# Moteino-IAQ-Shield.net
KiCad netlist of a schematic drawn in EAGLE
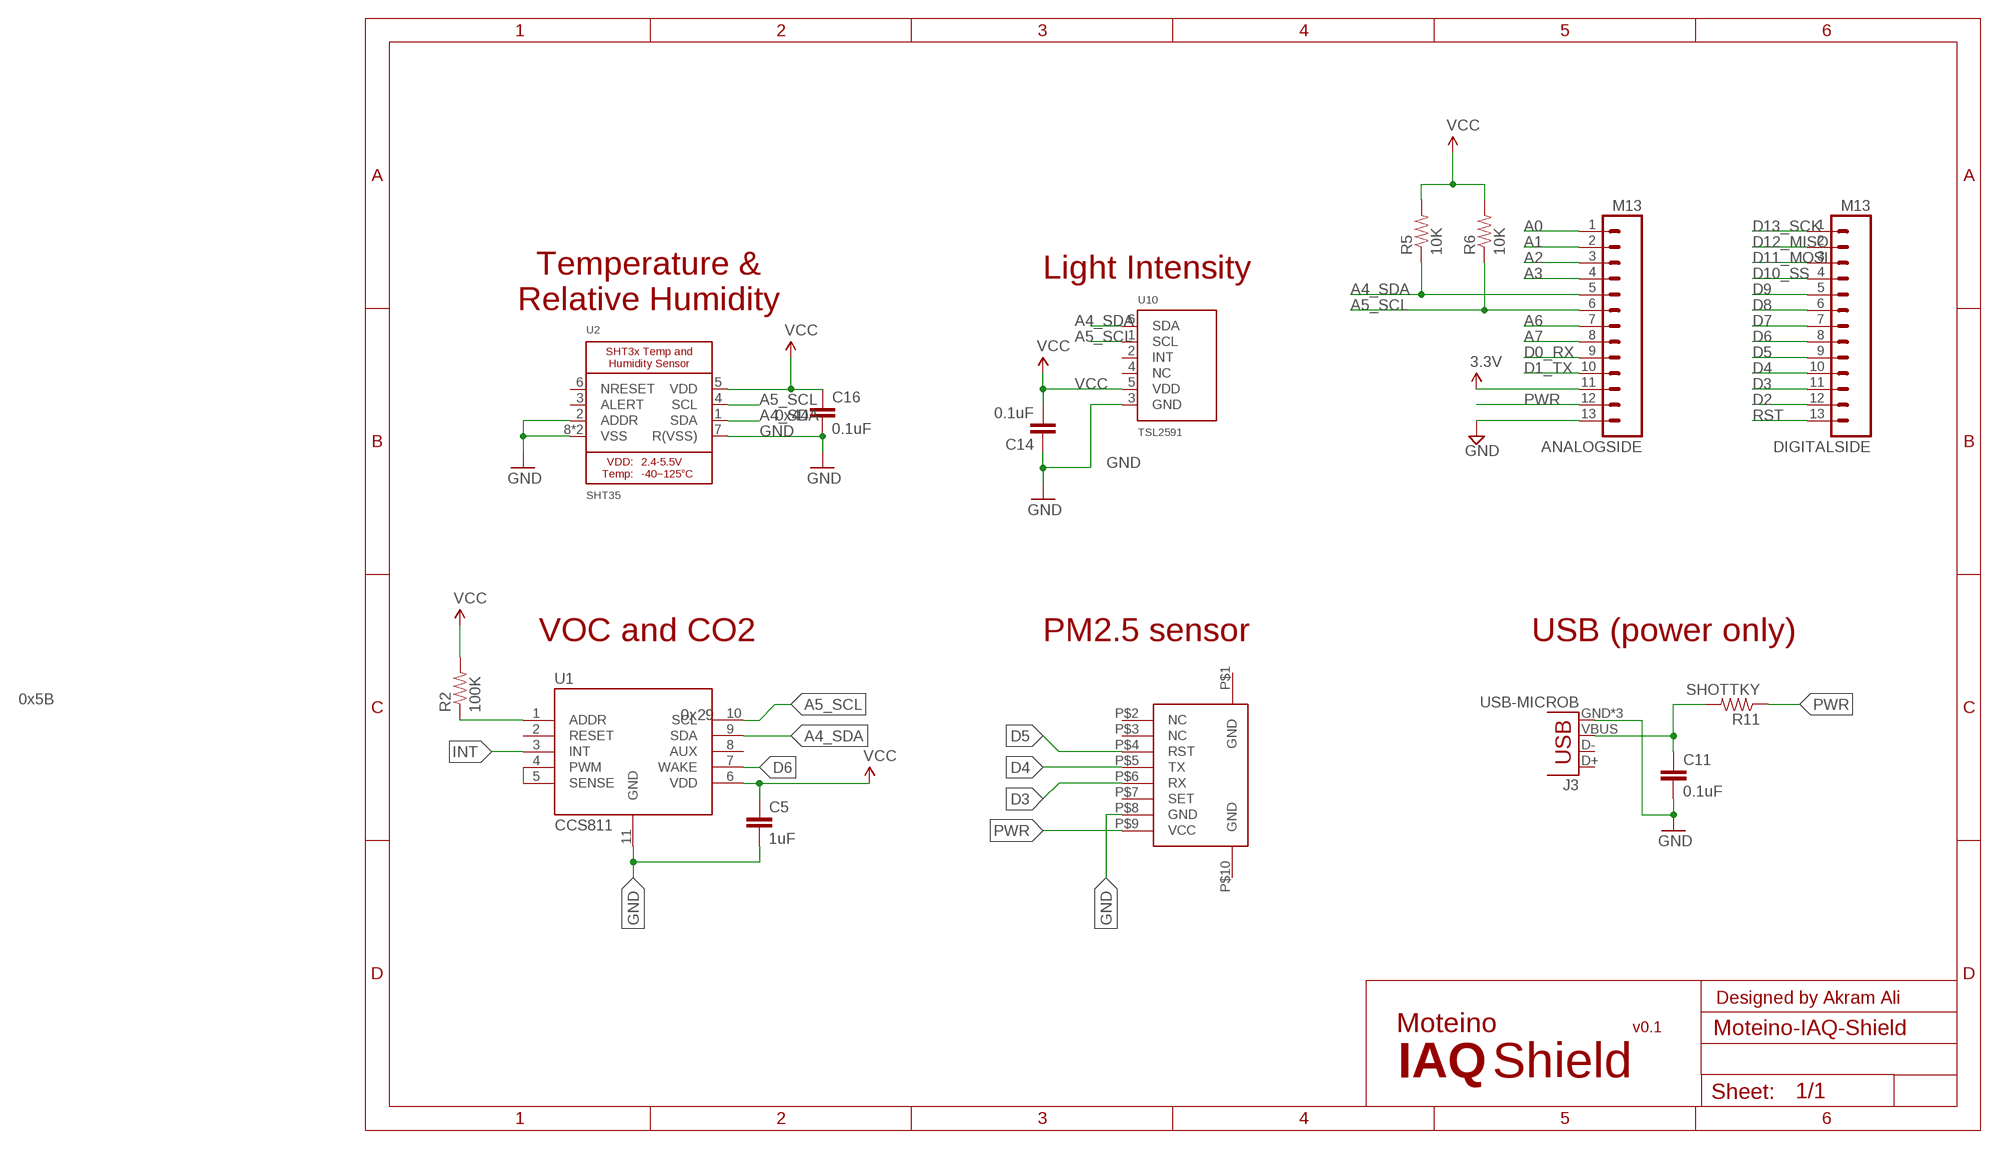
[diagram p0: schematic, sheet 1]

(export (version "E")
  (design (tool "Eeschema 10.0.6"))
  (components
    (comp (ref "ANALOGSIDE")
      (value "M13")
      (footprint "eagle-import:1X13")
      (libsource (lib "eagle-import") (part "M13"))
    )
    (comp (ref "C5")
      (value "1uF")
      (footprint "eagle-import:0805")
      (fields (field (name "MPN") "CC0805KKX7R7BB105"))
      (libsource (lib "eagle-import") (part "SparkFun-Passives_CAP0805"))
    )
    (comp (ref "C11")
      (value "0.1uF")
      (footprint "eagle-import:0805")
      (fields (field (name "MPN") "CC0805KRX7R9BB104"))
      (libsource (lib "eagle-import") (part "CAP0805"))
    )
    (comp (ref "C14")
      (value "0.1uF")
      (footprint "eagle-import:0805")
      (fields (field (name "MPN") "CC0805KRX7R9BB104"))
      (libsource (lib "eagle-import") (part "SparkFun-Passives_CAP0805"))
    )
    (comp (ref "C16")
      (value "0.1uF")
      (footprint "eagle-import:0805")
      (fields (field (name "MPN") "CC0805KRX7R9BB104"))
      (libsource (lib "eagle-import") (part "SparkFun-Passives_CAP0805"))
    )
    (comp (ref "DIGITALSIDE")
      (value "M13")
      (footprint "eagle-import:1X13")
      (libsource (lib "eagle-import") (part "M13"))
    )
    (comp (ref "J3")
      (value "USB-MICROB")
      (footprint "eagle-import:USB-MICROB")
      (fields (field (name "MPN") "47346-0001"))
      (libsource (lib "eagle-import") (part "USB-MICROB"))
    )
    (comp (ref "R2")
      (value "100K")
      (footprint "eagle-import:0805")
      (fields (field (name "MPN") "311-100KCRCT-ND"))
      (libsource (lib "eagle-import") (part "RESISTOR0805-RES"))
    )
    (comp (ref "R5")
      (value "10K")
      (footprint "eagle-import:0805")
      (fields (field (name "MPN") "RC0805FR-0710KL"))
      (libsource (lib "eagle-import") (part "SparkFun-Resistors_RESISTOR0805-RES"))
    )
    (comp (ref "R6")
      (value "10K")
      (footprint "eagle-import:0805")
      (fields (field (name "MPN") "RC0805FR-0710KL"))
      (libsource (lib "eagle-import") (part "SparkFun-Resistors_RESISTOR0805-RES"))
    )
    (comp (ref "R11")
      (value "SHOTTKY")
      (footprint "eagle-import:0805")
      (fields (field (name "MPN") "SD0805S040S0R5"))
      (libsource (lib "eagle-import") (part "RESISTOR0805-RES"))
    )
    (comp (ref "U$1")
      (value "PMS5003/7003")
      (footprint "eagle-import:0532610871")
      (libsource (lib "eagle-import") (part "0532610871"))
    )
    (comp (ref "U1")
      (value "CCS811")
      (footprint "eagle-import:LGA")
      (libsource (lib "eagle-import") (part "CCS811-I2C"))
    )
    (comp (ref "U2")
      (value "SHT35")
      (footprint "eagle-import:SHT3X")
      (fields (field (name "MPN") "SHT35-DIS-B"))
      (libsource (lib "eagle-import") (part "SHT3X"))
    )
    (comp (ref "U10")
      (value "TSL2591")
      (footprint "eagle-import:DFN6_TAOS")
      (fields (field (name "MPN") "TSL25911FN "))
      (libsource (lib "eagle-import") (part "LIGHT_TSL2591"))
    )
  )
  (nets
    (net (code "1") (name "/A0") (class "Default")
      (node (ref "ANALOGSIDE") (pin "1") (pinfunction "1_1") (pintype "passive"))
    )
    (net (code "2") (name "/A1") (class "Default")
      (node (ref "ANALOGSIDE") (pin "2") (pinfunction "2_2") (pintype "passive"))
    )
    (net (code "3") (name "/A2") (class "Default")
      (node (ref "ANALOGSIDE") (pin "3") (pinfunction "3_3") (pintype "passive"))
    )
    (net (code "4") (name "/A3") (class "Default")
      (node (ref "ANALOGSIDE") (pin "4") (pinfunction "4_4") (pintype "passive"))
    )
    (net (code "5") (name "/A6") (class "Default")
      (node (ref "ANALOGSIDE") (pin "7") (pinfunction "7_7") (pintype "passive"))
    )
    (net (code "6") (name "/A7") (class "Default")
      (node (ref "ANALOGSIDE") (pin "8") (pinfunction "8_8") (pintype "passive"))
    )
    (net (code "7") (name "/D0_RX") (class "Default")
      (node (ref "ANALOGSIDE") (pin "9") (pinfunction "9_9") (pintype "passive"))
    )
    (net (code "8") (name "/D1_TX") (class "Default")
      (node (ref "ANALOGSIDE") (pin "10") (pinfunction "10_10") (pintype "passive"))
    )
    (net (code "9") (name "/D2") (class "Default")
      (node (ref "DIGITALSIDE") (pin "12") (pinfunction "12_12") (pintype "passive"))
    )
    (net (code "10") (name "/D7") (class "Default")
      (node (ref "DIGITALSIDE") (pin "7") (pinfunction "7_7") (pintype "passive"))
    )
    (net (code "11") (name "/D8") (class "Default")
      (node (ref "DIGITALSIDE") (pin "6") (pinfunction "6_6") (pintype "passive"))
    )
    (net (code "12") (name "/D9") (class "Default")
      (node (ref "DIGITALSIDE") (pin "5") (pinfunction "5_5") (pintype "passive"))
    )
    (net (code "13") (name "/D10_SS") (class "Default")
      (node (ref "DIGITALSIDE") (pin "4") (pinfunction "4_4") (pintype "passive"))
    )
    (net (code "14") (name "/D11_MOSI") (class "Default")
      (node (ref "DIGITALSIDE") (pin "3") (pinfunction "3_3") (pintype "passive"))
    )
    (net (code "15") (name "/D12_MISO") (class "Default")
      (node (ref "DIGITALSIDE") (pin "2") (pinfunction "2_2") (pintype "passive"))
    )
    (net (code "16") (name "/D13_SCK") (class "Default")
      (node (ref "DIGITALSIDE") (pin "1") (pinfunction "1_1") (pintype "passive"))
    )
    (net (code "17") (name "/RST") (class "Default")
      (node (ref "DIGITALSIDE") (pin "13") (pinfunction "13_13") (pintype "passive"))
    )
    (net (code "18") (name "3.3V") (class "Default")
      (node (ref "ANALOGSIDE") (pin "11") (pinfunction "11_11") (pintype "passive"))
      (node (ref "C14") (pin "2") (pinfunction "2_2") (pintype "passive"))
      (node (ref "C16") (pin "1") (pinfunction "1_1") (pintype "passive"))
      (node (ref "C5") (pin "1") (pinfunction "1_1") (pintype "passive"))
      (node (ref "R2") (pin "2") (pinfunction "2_2") (pintype "passive"))
      (node (ref "R5") (pin "2") (pinfunction "2_2") (pintype "passive"))
      (node (ref "R6") (pin "2") (pinfunction "2_2") (pintype "passive"))
      (node (ref "U1") (pin "6") (pinfunction "VDD_6") (pintype "bidirectional"))
      (node (ref "U10") (pin "5") (pinfunction "VDD_5") (pintype "power_in"))
      (node (ref "U2") (pin "5") (pinfunction "VDD_5") (pintype "power_in"))
    )
    (net (code "19") (name "A4_SDA") (class "Default")
      (node (ref "ANALOGSIDE") (pin "5") (pinfunction "5_5") (pintype "passive"))
      (node (ref "R5") (pin "1") (pinfunction "1_1") (pintype "passive"))
      (node (ref "U1") (pin "9") (pinfunction "SDA_9") (pintype "bidirectional"))
      (node (ref "U10") (pin "6") (pinfunction "SDA_6") (pintype "bidirectional"))
      (node (ref "U2") (pin "1") (pinfunction "SDA_1") (pintype "bidirectional"))
    )
    (net (code "20") (name "A5_SCL") (class "Default")
      (node (ref "ANALOGSIDE") (pin "6") (pinfunction "6_6") (pintype "passive"))
      (node (ref "R6") (pin "1") (pinfunction "1_1") (pintype "passive"))
      (node (ref "U1") (pin "10") (pinfunction "SCL_10") (pintype "bidirectional"))
      (node (ref "U10") (pin "1") (pinfunction "SCL_1") (pintype "bidirectional"))
      (node (ref "U2") (pin "4") (pinfunction "SCL_4") (pintype "bidirectional"))
    )
    (net (code "21") (name "D3") (class "Default")
      (node (ref "DIGITALSIDE") (pin "11") (pinfunction "11_11") (pintype "passive"))
      (node (ref "U$1") (pin "P$6") (pinfunction "RX_P$6") (pintype "bidirectional"))
    )
    (net (code "22") (name "D4") (class "Default")
      (node (ref "DIGITALSIDE") (pin "10") (pinfunction "10_10") (pintype "passive"))
      (node (ref "U$1") (pin "P$5") (pinfunction "TX_P$5") (pintype "bidirectional"))
    )
    (net (code "23") (name "D5") (class "Default")
      (node (ref "DIGITALSIDE") (pin "9") (pinfunction "9_9") (pintype "passive"))
      (node (ref "U$1") (pin "P$4") (pinfunction "RST_P$4") (pintype "bidirectional"))
    )
    (net (code "24") (name "D6") (class "Default")
      (node (ref "DIGITALSIDE") (pin "8") (pinfunction "8_8") (pintype "passive"))
      (node (ref "U1") (pin "7") (pinfunction "WAKE_7") (pintype "bidirectional"))
    )
    (net (code "25") (name "GND") (class "Default")
      (node (ref "ANALOGSIDE") (pin "13") (pinfunction "13_13") (pintype "passive"))
      (node (ref "C11") (pin "2") (pinfunction "2_2") (pintype "passive"))
      (node (ref "C14") (pin "1") (pinfunction "1_1") (pintype "passive"))
      (node (ref "C16") (pin "2") (pinfunction "2_2") (pintype "passive"))
      (node (ref "C5") (pin "2") (pinfunction "2_2") (pintype "passive"))
      (node (ref "J3") (pin "GND") (pinfunction "GND_GND") (pintype "bidirectional"))
      (node (ref "J3") (pin "MT1") (pinfunction "GND_MT1") (pintype "bidirectional"))
      (node (ref "J3") (pin "MT2") (pinfunction "GND_MT2") (pintype "bidirectional"))
      (node (ref "U$1") (pin "P$8") (pinfunction "GND_P$8") (pintype "bidirectional"))
      (node (ref "U1") (pin "11") (pinfunction "GND_11") (pintype "bidirectional"))
      (node (ref "U10") (pin "3") (pinfunction "GND_3") (pintype "power_in"))
      (node (ref "U2") (pin "2") (pinfunction "ADDR_2") (pintype "bidirectional"))
      (node (ref "U2") (pin "7") (pinfunction "R(VSS)_7") (pintype "bidirectional"))
      (node (ref "U2") (pin "8") (pinfunction "VSS_8") (pintype "power_in"))
      (node (ref "U2") (pin "THERMAL") (pinfunction "VSS_THERMAL") (pintype "power_in"))
    )
    (net (code "26") (name "INT") (class "Default")
      (node (ref "U1") (pin "3") (pinfunction "INT_3") (pintype "bidirectional"))
    )
    (net (code "27") (name "Net-(C11-Pad1)") (class "Default")
      (node (ref "C11") (pin "1") (pinfunction "1_1") (pintype "passive"))
      (node (ref "J3") (pin "VBUS") (pinfunction "VBUS_VBUS") (pintype "bidirectional"))
      (node (ref "R11") (pin "2") (pinfunction "2_2") (pintype "passive"))
    )
    (net (code "28") (name "Net-(U1-ADDR)") (class "Default")
      (node (ref "R2") (pin "1") (pinfunction "1_1") (pintype "passive"))
      (node (ref "U1") (pin "1") (pinfunction "ADDR_1") (pintype "bidirectional"))
    )
    (net (code "29") (name "Net-(U1-PWM)") (class "Default")
      (node (ref "U1") (pin "4") (pinfunction "PWM_4") (pintype "bidirectional"))
      (node (ref "U1") (pin "5") (pinfunction "SENSE_5") (pintype "bidirectional"))
    )
    (net (code "30") (name "PWR") (class "Default")
      (node (ref "ANALOGSIDE") (pin "12") (pinfunction "12_12") (pintype "passive"))
      (node (ref "R11") (pin "1") (pinfunction "1_1") (pintype "passive"))
      (node (ref "U$1") (pin "P$9") (pinfunction "VCC_P$9") (pintype "bidirectional"))
    )
    (net (code "31") (name "unconnected-(J3-PadD+)") (class "Default")
      (node (ref "J3") (pin "D+") (pinfunction "D+_D+") (pintype "bidirectional"))
    )
    (net (code "32") (name "unconnected-(J3-PadD-)") (class "Default")
      (node (ref "J3") (pin "D-") (pinfunction "D-_D-") (pintype "bidirectional"))
    )
    (net (code "33") (name "unconnected-(U$1-GND-PadP$1)") (class "Default")
      (node (ref "U$1") (pin "P$1") (pinfunction "GND_P$1") (pintype "bidirectional"))
    )
    (net (code "34") (name "unconnected-(U$1-GND-PadP$10)") (class "Default")
      (node (ref "U$1") (pin "P$10") (pinfunction "GND_P$10") (pintype "bidirectional"))
    )
    (net (code "35") (name "unconnected-(U$1-NC-PadP$2)") (class "Default")
      (node (ref "U$1") (pin "P$2") (pinfunction "NC_P$2") (pintype "bidirectional"))
    )
    (net (code "36") (name "unconnected-(U$1-NC-PadP$3)") (class "Default")
      (node (ref "U$1") (pin "P$3") (pinfunction "NC_P$3") (pintype "bidirectional"))
    )
    (net (code "37") (name "unconnected-(U$1-SET-PadP$7)") (class "Default")
      (node (ref "U$1") (pin "P$7") (pinfunction "SET_P$7") (pintype "bidirectional"))
    )
    (net (code "38") (name "unconnected-(U1-AUX-Pad8)") (class "Default")
      (node (ref "U1") (pin "8") (pinfunction "AUX_8") (pintype "bidirectional"))
    )
    (net (code "39") (name "unconnected-(U1-RESET-Pad2)") (class "Default")
      (node (ref "U1") (pin "2") (pinfunction "RESET_2") (pintype "bidirectional"))
    )
    (net (code "40") (name "unconnected-(U2-ALERT-Pad3)") (class "Default")
      (node (ref "U2") (pin "3") (pinfunction "ALERT_3") (pintype "bidirectional"))
    )
    (net (code "41") (name "unconnected-(U2-NRESET-Pad6)") (class "Default")
      (node (ref "U2") (pin "6") (pinfunction "NRESET_6") (pintype "bidirectional"))
    )
    (net (code "42") (name "unconnected-(U10-INT-Pad2)") (class "Default")
      (node (ref "U10") (pin "2") (pinfunction "INT_2") (pintype "output"))
    )
    (net (code "43") (name "unconnected-(U10-NC-Pad4)") (class "Default")
      (node (ref "U10") (pin "4") (pinfunction "NC_4") (pintype "no_connect"))
    )
  )
)
